# braids_v03_h405_upgrade.net
KiCad netlist of a schematic drawn in EAGLE
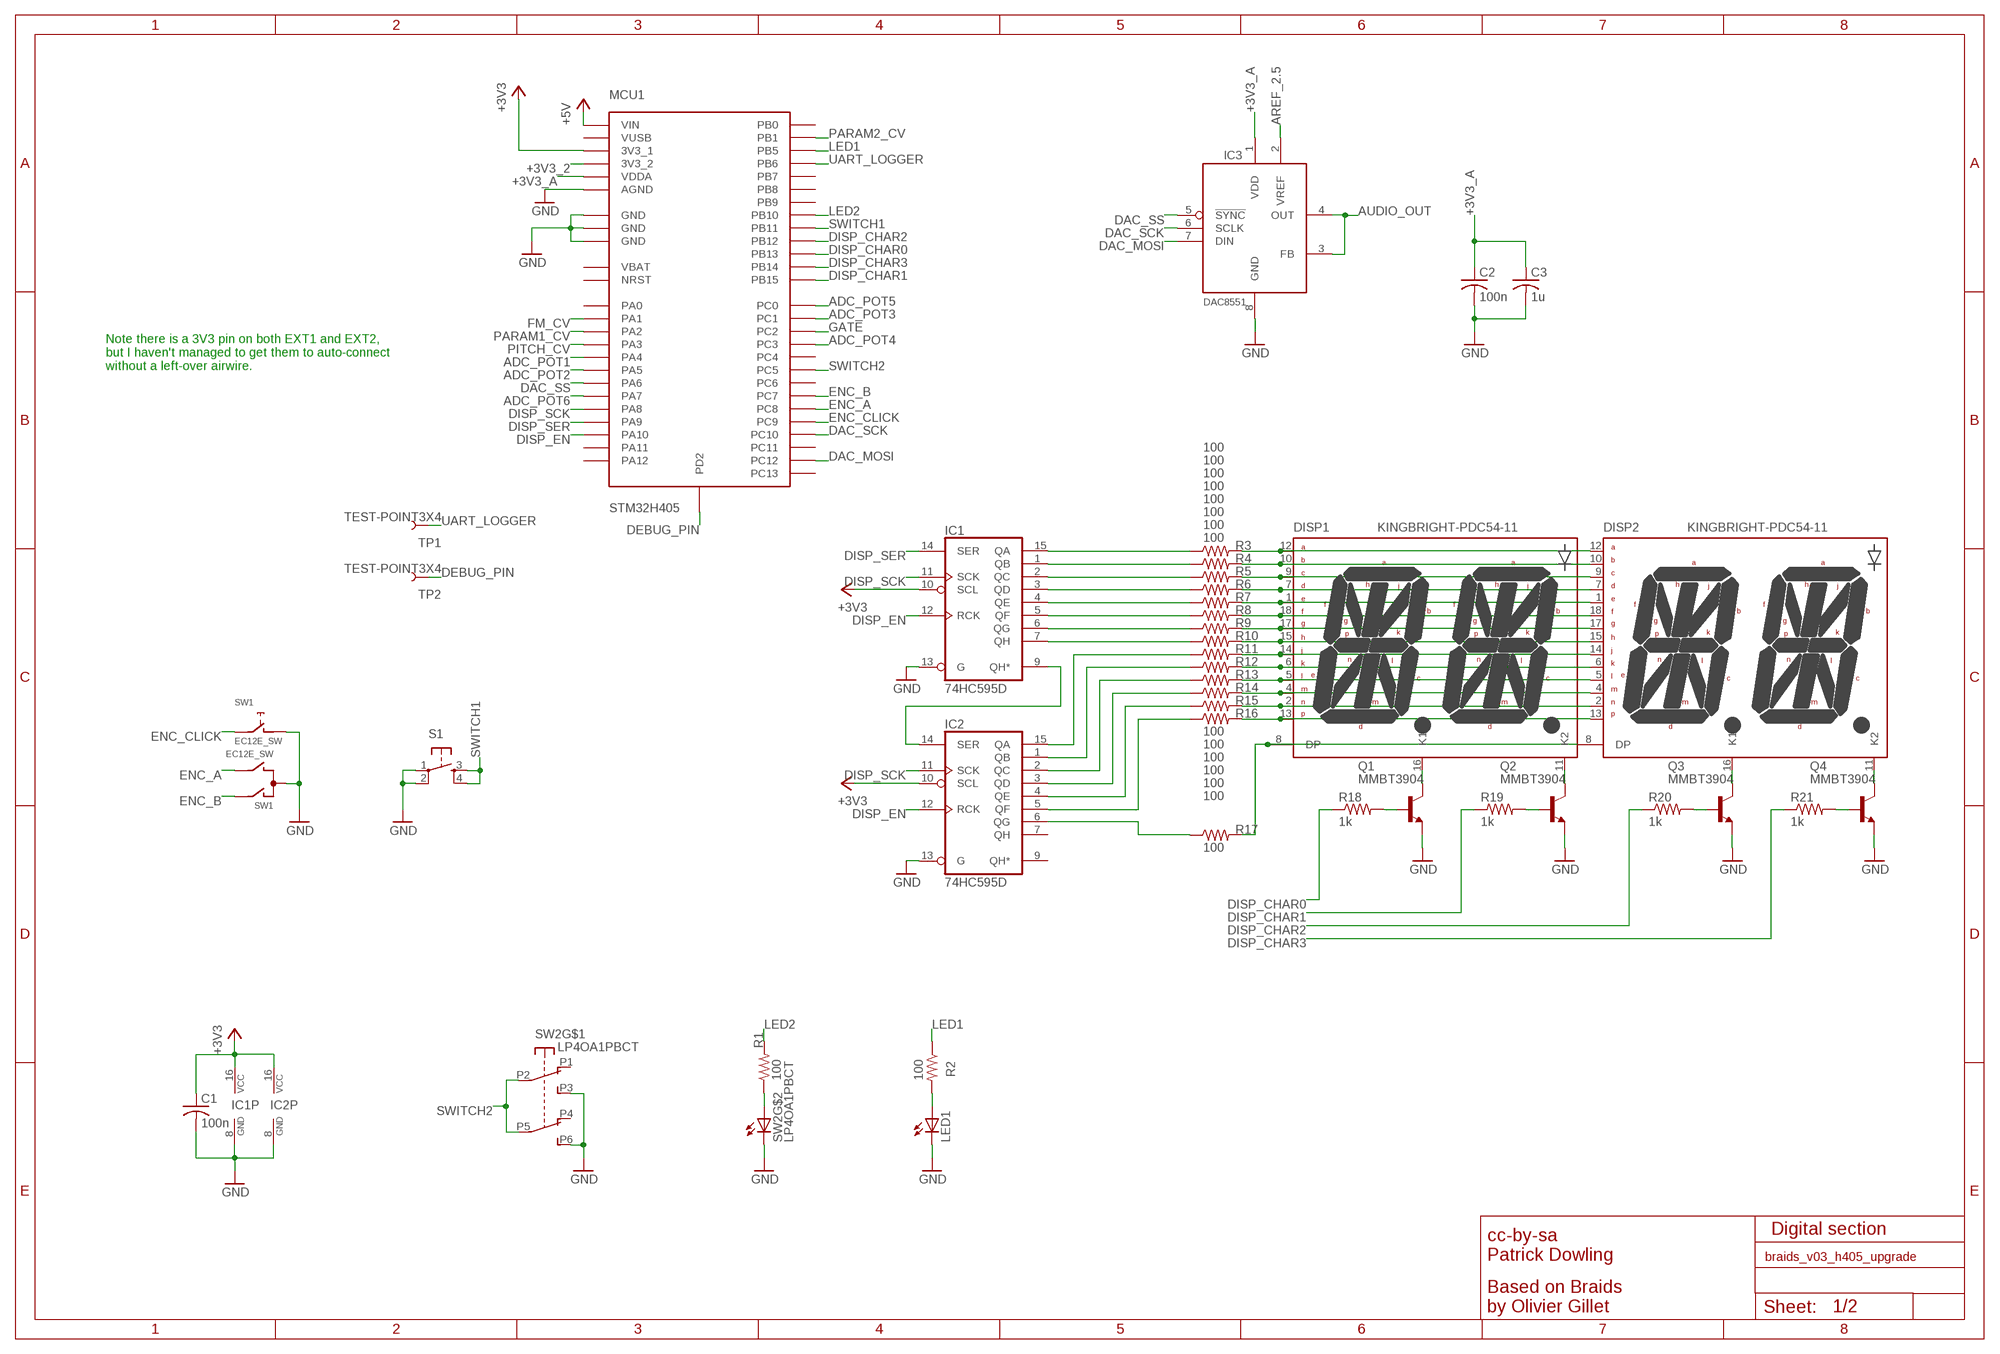
[diagram p0: schematic, sheet 1]
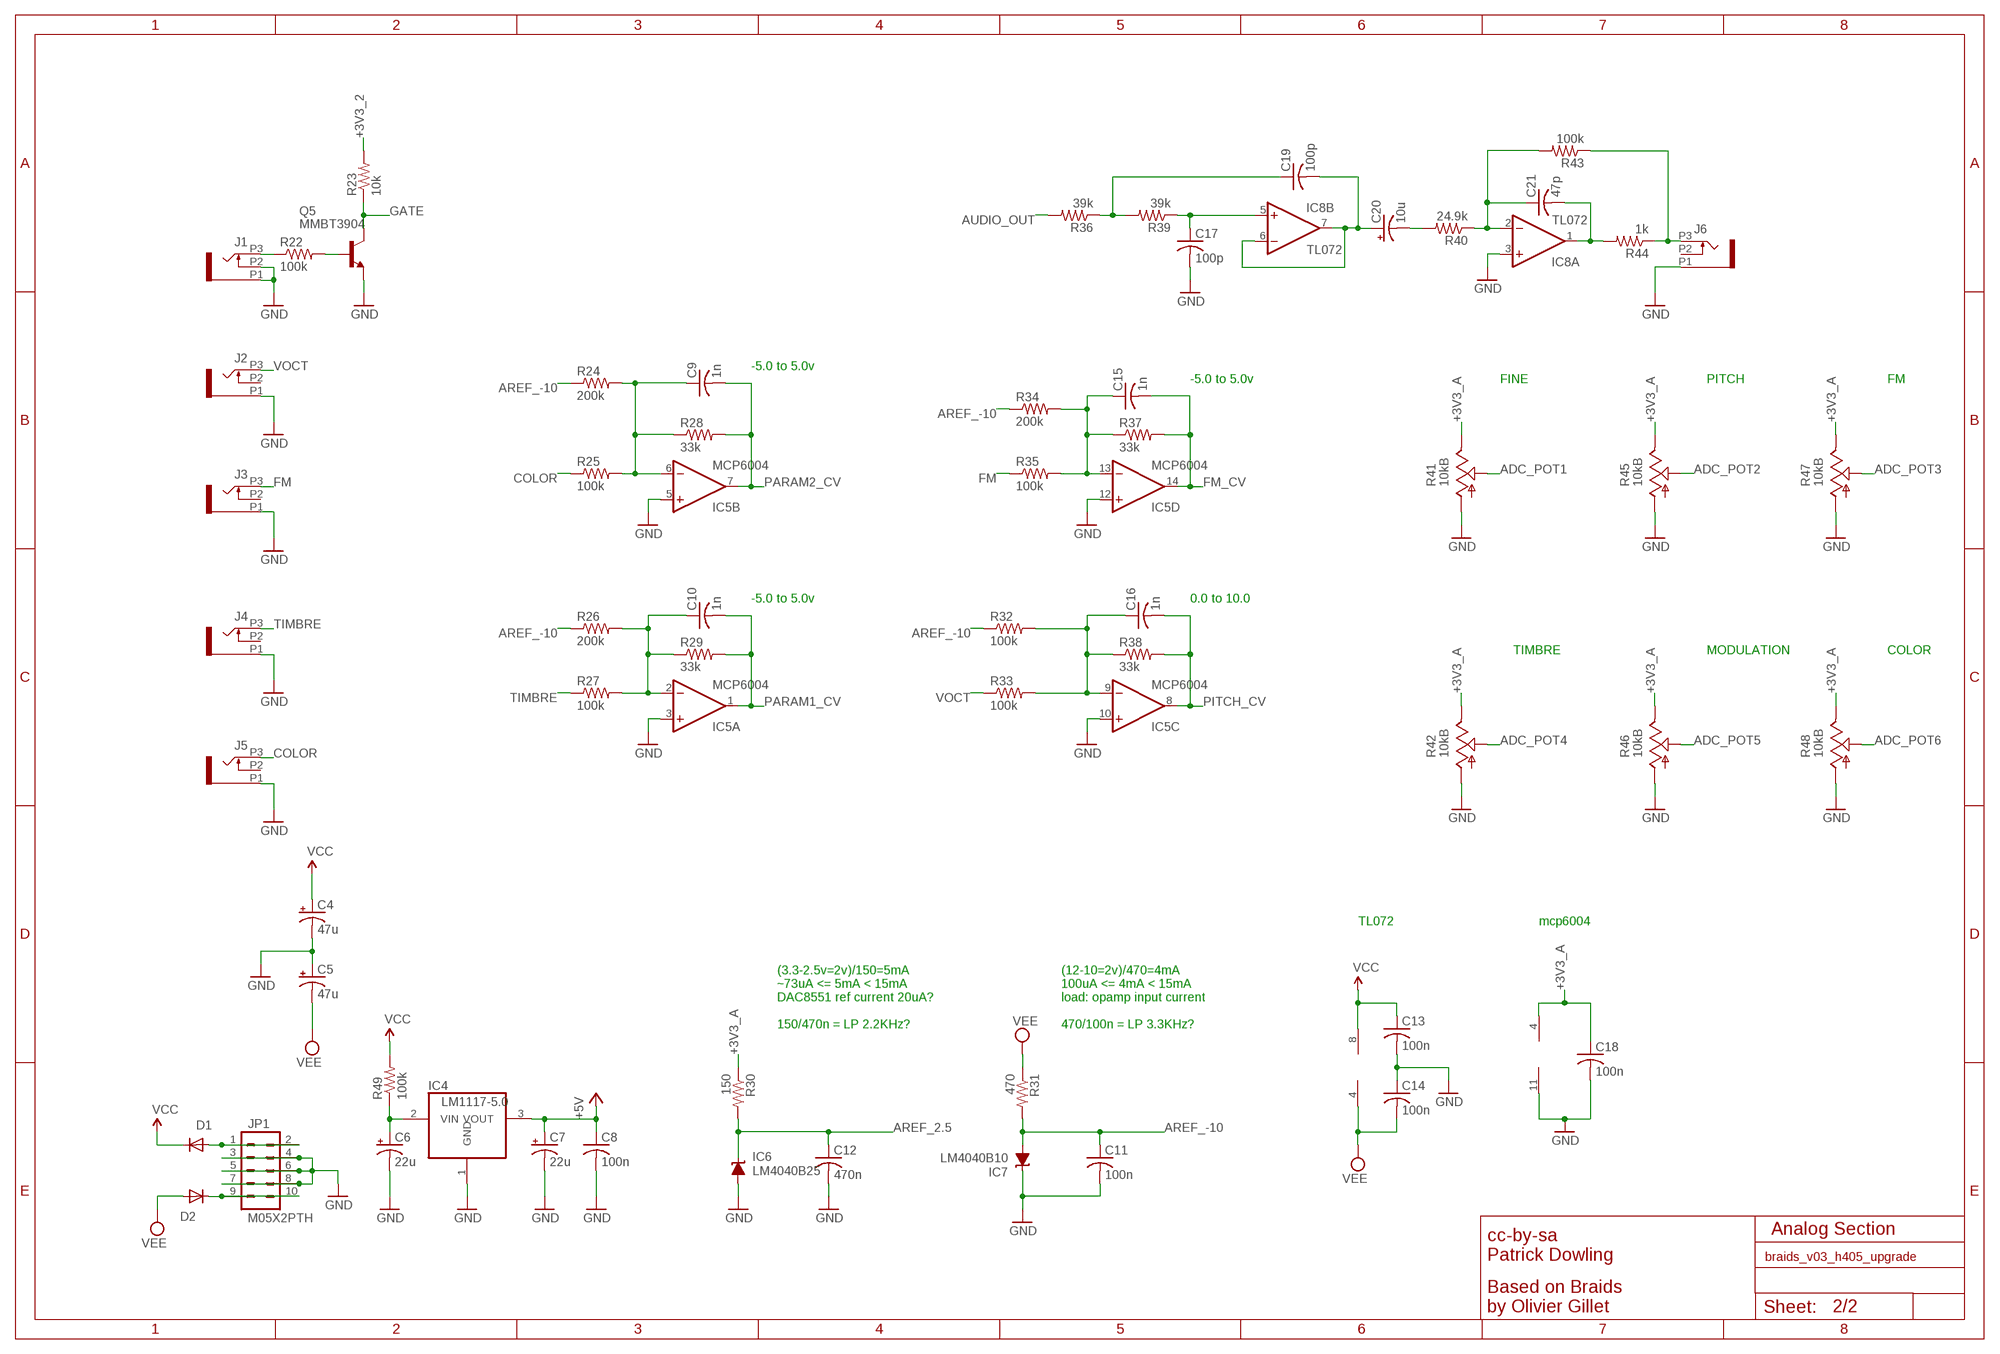
[diagram p1: schematic, sheet 2]

(export (version "E")
  (design (tool "Eeschema 10.0.6"))
  (components
    (comp (ref "C1")
      (value "100n")
      (footprint "eagle-import:C0805")
      (libsource (lib "eagle-import") (part "C-USC0805"))
    )
    (comp (ref "C2")
      (value "100n")
      (footprint "eagle-import:C0805")
      (libsource (lib "eagle-import") (part "C-USC0805"))
    )
    (comp (ref "C3")
      (value "1u")
      (footprint "eagle-import:C0805")
      (libsource (lib "eagle-import") (part "C-USC0805"))
    )
    (comp (ref "DISP1")
      (value "KINGBRIGHT-PDC54-11")
      (footprint "eagle-import:PDC54")
      (libsource (lib "eagle-import") (part "KINGBRIGHT-PDC54-11"))
    )
    (comp (ref "DISP2")
      (value "KINGBRIGHT-PDC54-11")
      (footprint "eagle-import:PDC54")
      (libsource (lib "eagle-import") (part "KINGBRIGHT-PDC54-11"))
    )
    (comp (ref "IC1")
      (value "74HC595D")
      (footprint "eagle-import:SO16")
      (libsource (lib "eagle-import") (part "74595DHC"))
    )
    (comp (ref "IC2")
      (value "74HC595D")
      (footprint "eagle-import:SO16")
      (libsource (lib "eagle-import") (part "74595DHC"))
    )
    (comp (ref "IC3")
      (value "DAC8551")
      (footprint "eagle-import:MSOP-8")
      (libsource (lib "eagle-import") (part "DAC855X"))
    )
    (comp (ref "LED1")
      (value "LED3MM")
      (footprint "eagle-import:LED3MM")
      (libsource (lib "eagle-import") (part "LED3MM"))
    )
    (comp (ref "MCU1")
      (value "STM32H405")
      (footprint "eagle-import:STM32H103")
      (libsource (lib "eagle-import") (part "STM32H103"))
    )
    (comp (ref "Q1")
      (value "MMBT3904")
      (footprint "eagle-import:SOT23-BEC")
      (libsource (lib "eagle-import") (part "-NPN-SOT23-BECMMBT3904LT1"))
    )
    (comp (ref "Q2")
      (value "MMBT3904")
      (footprint "eagle-import:SOT23-BEC")
      (libsource (lib "eagle-import") (part "-NPN-SOT23-BECMMBT3904LT1"))
    )
    (comp (ref "Q3")
      (value "MMBT3904")
      (footprint "eagle-import:SOT23-BEC")
      (libsource (lib "eagle-import") (part "-NPN-SOT23-BECMMBT3904LT1"))
    )
    (comp (ref "Q4")
      (value "MMBT3904")
      (footprint "eagle-import:SOT23-BEC")
      (libsource (lib "eagle-import") (part "-NPN-SOT23-BECMMBT3904LT1"))
    )
    (comp (ref "R1")
      (value "100")
      (footprint "eagle-import:R0805")
      (libsource (lib "eagle-import") (part "R-US_R0805"))
    )
    (comp (ref "R2")
      (value "100")
      (footprint "eagle-import:R0603")
      (libsource (lib "eagle-import") (part "R-US_R0603"))
    )
    (comp (ref "R3")
      (value "100")
      (footprint "eagle-import:R0603")
      (libsource (lib "eagle-import") (part "R-US_R0603"))
    )
    (comp (ref "R4")
      (value "100")
      (footprint "eagle-import:R0603")
      (libsource (lib "eagle-import") (part "R-US_R0603"))
    )
    (comp (ref "R5")
      (value "100")
      (footprint "eagle-import:R0603")
      (libsource (lib "eagle-import") (part "R-US_R0603"))
    )
    (comp (ref "R6")
      (value "100")
      (footprint "eagle-import:R0603")
      (libsource (lib "eagle-import") (part "R-US_R0603"))
    )
    (comp (ref "R7")
      (value "100")
      (footprint "eagle-import:R0603")
      (libsource (lib "eagle-import") (part "R-US_R0603"))
    )
    (comp (ref "R8")
      (value "100")
      (footprint "eagle-import:R0603")
      (libsource (lib "eagle-import") (part "R-US_R0603"))
    )
    (comp (ref "R9")
      (value "100")
      (footprint "eagle-import:R0603")
      (libsource (lib "eagle-import") (part "R-US_R0603"))
    )
    (comp (ref "R10")
      (value "100")
      (footprint "eagle-import:R0603")
      (libsource (lib "eagle-import") (part "R-US_R0603"))
    )
    (comp (ref "R11")
      (value "100")
      (footprint "eagle-import:R0603")
      (libsource (lib "eagle-import") (part "R-US_R0603"))
    )
    (comp (ref "R12")
      (value "100")
      (footprint "eagle-import:R0603")
      (libsource (lib "eagle-import") (part "R-US_R0603"))
    )
    (comp (ref "R13")
      (value "100")
      (footprint "eagle-import:R0603")
      (libsource (lib "eagle-import") (part "R-US_R0603"))
    )
    (comp (ref "R14")
      (value "100")
      (footprint "eagle-import:R0603")
      (libsource (lib "eagle-import") (part "R-US_R0603"))
    )
    (comp (ref "R15")
      (value "100")
      (footprint "eagle-import:R0603")
      (libsource (lib "eagle-import") (part "R-US_R0603"))
    )
    (comp (ref "R16")
      (value "100")
      (footprint "eagle-import:R0603")
      (libsource (lib "eagle-import") (part "R-US_R0603"))
    )
    (comp (ref "R17")
      (value "100")
      (footprint "eagle-import:R0603")
      (libsource (lib "eagle-import") (part "R-US_R0603"))
    )
    (comp (ref "R18")
      (value "1k")
      (footprint "eagle-import:R0603")
      (libsource (lib "eagle-import") (part "R-US_R0603"))
    )
    (comp (ref "R19")
      (value "1k")
      (footprint "eagle-import:R0603")
      (libsource (lib "eagle-import") (part "R-US_R0603"))
    )
    (comp (ref "R20")
      (value "1k")
      (footprint "eagle-import:R0603")
      (libsource (lib "eagle-import") (part "R-US_R0603"))
    )
    (comp (ref "R21")
      (value "1k")
      (footprint "eagle-import:R0603")
      (libsource (lib "eagle-import") (part "R-US_R0603"))
    )
    (comp (ref "S1")
      (value "TAC_SWITCHPTH")
      (footprint "eagle-import:TACTILE-PTH")
      (libsource (lib "eagle-import") (part "TAC_SWITCHPTH"))
    )
    (comp (ref "SW1")
      (value "EC12E_SW")
      (footprint "eagle-import:ALPS_EC12E_SW")
      (libsource (lib "eagle-import") (part "EC12E_SW"))
    )
    (comp (ref "SW2")
      (value "LP4OA1PBCT")
      (footprint "eagle-import:LP4OA1PBCT")
      (libsource (lib "eagle-import") (part "LP4OA1PBCT"))
    )
    (comp (ref "TP1")
      (value "TEST-POINT3X4")
      (footprint "eagle-import:PAD.03X.04")
      (libsource (lib "eagle-import") (part "TEST-POINT3X4"))
    )
    (comp (ref "TP2")
      (value "TEST-POINT3X4")
      (footprint "eagle-import:PAD.03X.04")
      (libsource (lib "eagle-import") (part "TEST-POINT3X4"))
    )
    (comp (ref "C4")
      (value "47u")
      (footprint "eagle-import:PANASONIC_D")
      (libsource (lib "eagle-import") (part "CPOL-USD"))
    )
    (comp (ref "C5")
      (value "47u")
      (footprint "eagle-import:PANASONIC_D")
      (libsource (lib "eagle-import") (part "CPOL-USD"))
    )
    (comp (ref "C6")
      (value "22u")
      (footprint "eagle-import:PANASONIC_C")
      (libsource (lib "eagle-import") (part "CPOL-USC"))
    )
    (comp (ref "C7")
      (value "22u")
      (footprint "eagle-import:PANASONIC_C")
      (libsource (lib "eagle-import") (part "CPOL-USC"))
    )
    (comp (ref "C8")
      (value "100n")
      (footprint "eagle-import:C0805")
      (libsource (lib "eagle-import") (part "C-USC0805"))
    )
    (comp (ref "C9")
      (value "1n")
      (footprint "eagle-import:C0805")
      (libsource (lib "eagle-import") (part "C-USC0805"))
    )
    (comp (ref "C10")
      (value "1n")
      (footprint "eagle-import:C0805")
      (libsource (lib "eagle-import") (part "C-USC0805"))
    )
    (comp (ref "C11")
      (value "100n")
      (footprint "eagle-import:C0805")
      (libsource (lib "eagle-import") (part "C-USC0805"))
    )
    (comp (ref "C12")
      (value "470n")
      (footprint "eagle-import:C0805")
      (libsource (lib "eagle-import") (part "C-USC0805"))
    )
    (comp (ref "C13")
      (value "100n")
      (footprint "eagle-import:C0805")
      (libsource (lib "eagle-import") (part "C-USC0805"))
    )
    (comp (ref "C14")
      (value "100n")
      (footprint "eagle-import:C0805")
      (libsource (lib "eagle-import") (part "C-USC0805"))
    )
    (comp (ref "C15")
      (value "1n")
      (footprint "eagle-import:C0805")
      (libsource (lib "eagle-import") (part "C-USC0805"))
    )
    (comp (ref "C16")
      (value "1n")
      (footprint "eagle-import:C0805")
      (libsource (lib "eagle-import") (part "C-USC0805"))
    )
    (comp (ref "C17")
      (value "100p")
      (footprint "eagle-import:C0805")
      (libsource (lib "eagle-import") (part "C-USC0805"))
    )
    (comp (ref "C18")
      (value "100n")
      (footprint "eagle-import:C0805")
      (libsource (lib "eagle-import") (part "C-USC0805"))
    )
    (comp (ref "C19")
      (value "100p")
      (footprint "eagle-import:C0805")
      (libsource (lib "eagle-import") (part "C-USC0805"))
    )
    (comp (ref "C20")
      (value "10u")
      (footprint "eagle-import:E2-5")
      (libsource (lib "eagle-import") (part "CPOL-USE2-5"))
    )
    (comp (ref "C21")
      (value "47p")
      (footprint "eagle-import:C0805")
      (libsource (lib "eagle-import") (part "C-USC0805"))
    )
    (comp (ref "D1")
      (value "1N5819HW")
      (footprint "eagle-import:SOD123")
      (libsource (lib "eagle-import") (part "DIODE-SOD123"))
    )
    (comp (ref "D2")
      (value "1N5819HW")
      (footprint "eagle-import:SOD123")
      (libsource (lib "eagle-import") (part "DIODE-SOD123"))
    )
    (comp (ref "IC4")
      (value "LM1117-5.0")
      (footprint "eagle-import:TO252")
      (libsource (lib "eagle-import") (part "REG1117T"))
    )
    (comp (ref "IC5")
      (value "MCP6004")
      (footprint "eagle-import:SO14")
      (libsource (lib "eagle-import") (part "TL074D"))
    )
    (comp (ref "IC6")
      (value "LM4040B25")
      (footprint "eagle-import:DBZ_R-PDSO-G3")
      (libsource (lib "eagle-import") (part "LM4041DBZB12"))
    )
    (comp (ref "IC7")
      (value "LM4040B10")
      (footprint "eagle-import:DBZ_R-PDSO-G3")
      (libsource (lib "eagle-import") (part "LM4041DBZB12"))
    )
    (comp (ref "IC8")
      (value "TL072")
      (footprint "eagle-import:SO08")
      (libsource (lib "eagle-import") (part "TL072D"))
    )
    (comp (ref "J1")
      (value "PJ301_THONKICONN6")
      (footprint "eagle-import:WQP_PJ_301M6")
      (libsource (lib "eagle-import") (part "PJ301_THONKICONN6"))
    )
    (comp (ref "J2")
      (value "PJ301_THONKICONN6")
      (footprint "eagle-import:WQP_PJ_301M6")
      (libsource (lib "eagle-import") (part "PJ301_THONKICONN6"))
    )
    (comp (ref "J3")
      (value "PJ301_THONKICONN6")
      (footprint "eagle-import:WQP_PJ_301M6")
      (libsource (lib "eagle-import") (part "PJ301_THONKICONN6"))
    )
    (comp (ref "J4")
      (value "PJ301_THONKICONN6")
      (footprint "eagle-import:WQP_PJ_301M6")
      (libsource (lib "eagle-import") (part "PJ301_THONKICONN6"))
    )
    (comp (ref "J5")
      (value "PJ301_THONKICONN6")
      (footprint "eagle-import:WQP_PJ_301M6")
      (libsource (lib "eagle-import") (part "PJ301_THONKICONN6"))
    )
    (comp (ref "J6")
      (value "PJ301_THONKICONN6")
      (footprint "eagle-import:WQP_PJ_301M6")
      (libsource (lib "eagle-import") (part "PJ301_THONKICONN6"))
    )
    (comp (ref "JP1")
      (value "M05X2PTH")
      (footprint "eagle-import:AVR_ICSP")
      (libsource (lib "eagle-import") (part "M05X2PTH"))
    )
    (comp (ref "Q5")
      (value "MMBT3904")
      (footprint "eagle-import:SOT23-BEC")
      (libsource (lib "eagle-import") (part "-NPN-SOT23-BECMMBT3904LT1"))
    )
    (comp (ref "R22")
      (value "100k")
      (footprint "eagle-import:R0805")
      (libsource (lib "eagle-import") (part "R-US_R0805"))
    )
    (comp (ref "R23")
      (value "10k")
      (footprint "eagle-import:R0805")
      (libsource (lib "eagle-import") (part "R-US_R0805"))
    )
    (comp (ref "R24")
      (value "200k")
      (footprint "eagle-import:R0805")
      (libsource (lib "eagle-import") (part "R-US_R0805"))
    )
    (comp (ref "R25")
      (value "100k")
      (footprint "eagle-import:R0805")
      (libsource (lib "eagle-import") (part "R-US_R0805"))
    )
    (comp (ref "R26")
      (value "200k")
      (footprint "eagle-import:R0805")
      (libsource (lib "eagle-import") (part "R-US_R0805"))
    )
    (comp (ref "R27")
      (value "100k")
      (footprint "eagle-import:R0805")
      (libsource (lib "eagle-import") (part "R-US_R0805"))
    )
    (comp (ref "R28")
      (value "33k")
      (footprint "eagle-import:R0805")
      (libsource (lib "eagle-import") (part "R-US_R0805"))
    )
    (comp (ref "R29")
      (value "33k")
      (footprint "eagle-import:R0805")
      (libsource (lib "eagle-import") (part "R-US_R0805"))
    )
    (comp (ref "R30")
      (value "150")
      (footprint "eagle-import:R0805")
      (libsource (lib "eagle-import") (part "R-US_R0805"))
    )
    (comp (ref "R31")
      (value "470")
      (footprint "eagle-import:R0805")
      (libsource (lib "eagle-import") (part "R-US_R0805"))
    )
    (comp (ref "R32")
      (value "100k")
      (footprint "eagle-import:R0805")
      (libsource (lib "eagle-import") (part "R-US_R0805"))
    )
    (comp (ref "R33")
      (value "100k")
      (footprint "eagle-import:R0805")
      (libsource (lib "eagle-import") (part "R-US_R0805"))
    )
    (comp (ref "R34")
      (value "200k")
      (footprint "eagle-import:R0805")
      (libsource (lib "eagle-import") (part "R-US_R0805"))
    )
    (comp (ref "R35")
      (value "100k")
      (footprint "eagle-import:R0805")
      (libsource (lib "eagle-import") (part "R-US_R0805"))
    )
    (comp (ref "R36")
      (value "39k")
      (footprint "eagle-import:R0805")
      (libsource (lib "eagle-import") (part "R-US_R0805"))
    )
    (comp (ref "R37")
      (value "33k")
      (footprint "eagle-import:R0805")
      (libsource (lib "eagle-import") (part "R-US_R0805"))
    )
    (comp (ref "R38")
      (value "33k")
      (footprint "eagle-import:R0805")
      (libsource (lib "eagle-import") (part "R-US_R0805"))
    )
    (comp (ref "R39")
      (value "39k")
      (footprint "eagle-import:R0805")
      (libsource (lib "eagle-import") (part "R-US_R0805"))
    )
    (comp (ref "R40")
      (value "24.9k")
      (footprint "eagle-import:R0805")
      (libsource (lib "eagle-import") (part "R-US_R0805"))
    )
    (comp (ref "R41")
      (value "10kB")
      (footprint "eagle-import:ALPS_POT_VERTICAL_PS")
      (libsource (lib "eagle-import") (part "POT_USVERTICAL_PS"))
    )
    (comp (ref "R42")
      (value "10kB")
      (footprint "eagle-import:ALPS_POT_VERTICAL_PS")
      (libsource (lib "eagle-import") (part "POT_USVERTICAL_PS"))
    )
    (comp (ref "R43")
      (value "100k")
      (footprint "eagle-import:R0805")
      (libsource (lib "eagle-import") (part "R-US_R0805"))
    )
    (comp (ref "R44")
      (value "1k")
      (footprint "eagle-import:R0805")
      (libsource (lib "eagle-import") (part "R-US_R0805"))
    )
    (comp (ref "R45")
      (value "10kB")
      (footprint "eagle-import:ALPS_POT_VERTICAL_PS")
      (libsource (lib "eagle-import") (part "POT_USVERTICAL_PS"))
    )
    (comp (ref "R46")
      (value "10kB")
      (footprint "eagle-import:ALPS_POT_VERTICAL_PS")
      (libsource (lib "eagle-import") (part "POT_USVERTICAL_PS"))
    )
    (comp (ref "R47")
      (value "10kB")
      (footprint "eagle-import:ALPS_POT_VERTICAL_PS")
      (libsource (lib "eagle-import") (part "POT_USVERTICAL_PS"))
    )
    (comp (ref "R48")
      (value "10kB")
      (footprint "eagle-import:ALPS_POT_VERTICAL_PS")
      (libsource (lib "eagle-import") (part "POT_USVERTICAL_PS"))
    )
    (comp (ref "R49")
      (value "100k")
      (footprint "eagle-import:R1206")
      (libsource (lib "eagle-import") (part "R-US_R1206"))
    )
  )
  (nets
    (net (code "1") (name "+3V3") (class "Default")
      (node (ref "C1") (pin "1") (pinfunction "1_1") (pintype "passive"))
      (node (ref "IC1") (pin "10") (pinfunction "SCL_10") (pintype "input"))
      (node (ref "IC1") (pin "16") (pinfunction "VCC_16") (pintype "power_in"))
      (node (ref "IC2") (pin "10") (pinfunction "SCL_10") (pintype "input"))
      (node (ref "IC2") (pin "16") (pinfunction "VCC_16") (pintype "power_in"))
      (node (ref "MCU1") (pin "EXT1-5") (pinfunction "3V3_1_EXT1-5") (pintype "power_in"))
    )
    (net (code "2") (name "+3V3_2") (class "Default")
      (node (ref "MCU1") (pin "EXT2-5") (pinfunction "3V3_2_EXT2-5") (pintype "power_in"))
      (node (ref "R23") (pin "2") (pinfunction "2_2") (pintype "passive"))
    )
    (net (code "3") (name "+3V3_A") (class "Default")
      (node (ref "C18") (pin "1") (pinfunction "1_1") (pintype "passive"))
      (node (ref "C2") (pin "1") (pinfunction "1_1") (pintype "passive"))
      (node (ref "C3") (pin "1") (pinfunction "1_1") (pintype "passive"))
      (node (ref "IC3") (pin "1") (pinfunction "VDD_1") (pintype "power_in"))
      (node (ref "IC5") (pin "4") (pinfunction "V+_4") (pintype "power_in"))
      (node (ref "MCU1") (pin "EXT2-1") (pinfunction "VDDA_EXT2-1") (pintype "power_in"))
      (node (ref "R30") (pin "1") (pinfunction "1_1") (pintype "passive"))
      (node (ref "R41") (pin "P$1") (pinfunction "E_P$1") (pintype "passive"))
      (node (ref "R42") (pin "P$1") (pinfunction "E_P$1") (pintype "passive"))
      (node (ref "R45") (pin "P$1") (pinfunction "E_P$1") (pintype "passive"))
      (node (ref "R46") (pin "P$1") (pinfunction "E_P$1") (pintype "passive"))
      (node (ref "R47") (pin "P$1") (pinfunction "E_P$1") (pintype "passive"))
      (node (ref "R48") (pin "P$1") (pinfunction "E_P$1") (pintype "passive"))
    )
    (net (code "4") (name "+5V") (class "Default")
      (node (ref "C7") (pin "+") (pinfunction "+_+") (pintype "passive"))
      (node (ref "C8") (pin "1") (pinfunction "1_1") (pintype "passive"))
      (node (ref "IC4") (pin "3") (pinfunction "VOUT_3") (pintype "output"))
      (node (ref "MCU1") (pin "EXT2-26") (pinfunction "VIN_EXT2-26") (pintype "power_in"))
    )
    (net (code "5") (name "ADC_POT1") (class "Default")
      (node (ref "MCU1") (pin "EXT2-11") (pinfunction "PA4_EXT2-11") (pintype "bidirectional"))
      (node (ref "R41") (pin "P$2") (pinfunction "S_P$2") (pintype "passive"))
    )
    (net (code "6") (name "ADC_POT2") (class "Default")
      (node (ref "MCU1") (pin "EXT1-18") (pinfunction "PA5_EXT1-18") (pintype "bidirectional"))
      (node (ref "R45") (pin "P$2") (pinfunction "S_P$2") (pintype "passive"))
    )
    (net (code "7") (name "ADC_POT3") (class "Default")
      (node (ref "MCU1") (pin "EXT1-20") (pinfunction "PC1_EXT1-20") (pintype "bidirectional"))
      (node (ref "R47") (pin "P$2") (pinfunction "S_P$2") (pintype "passive"))
    )
    (net (code "8") (name "ADC_POT4") (class "Default")
      (node (ref "MCU1") (pin "EXT2-9") (pinfunction "PC3_EXT2-9") (pintype "bidirectional"))
      (node (ref "R42") (pin "P$2") (pinfunction "S_P$2") (pintype "passive"))
    )
    (net (code "9") (name "ADC_POT5") (class "Default")
      (node (ref "MCU1") (pin "EXT1-19") (pinfunction "PC0_EXT1-19") (pintype "bidirectional"))
      (node (ref "R46") (pin "P$2") (pinfunction "S_P$2") (pintype "passive"))
    )
    (net (code "10") (name "ADC_POT6") (class "Default")
      (node (ref "MCU1") (pin "EXT1-22") (pinfunction "PA7_EXT1-22") (pintype "bidirectional"))
      (node (ref "R48") (pin "P$2") (pinfunction "S_P$2") (pintype "passive"))
    )
    (net (code "11") (name "AREF_-10") (class "Default")
      (node (ref "C11") (pin "1") (pinfunction "1_1") (pintype "passive"))
      (node (ref "IC7") (pin "2") (pinfunction "A_2") (pintype "passive"))
      (node (ref "R24") (pin "1") (pinfunction "1_1") (pintype "passive"))
      (node (ref "R26") (pin "1") (pinfunction "1_1") (pintype "passive"))
      (node (ref "R31") (pin "2") (pinfunction "2_2") (pintype "passive"))
      (node (ref "R32") (pin "1") (pinfunction "1_1") (pintype "passive"))
      (node (ref "R34") (pin "1") (pinfunction "1_1") (pintype "passive"))
    )
    (net (code "12") (name "AREF_2.5") (class "Default")
      (node (ref "C12") (pin "1") (pinfunction "1_1") (pintype "passive"))
      (node (ref "IC3") (pin "2") (pinfunction "VREF_2") (pintype "power_in"))
      (node (ref "IC6") (pin "1") (pinfunction "C_1") (pintype "passive"))
      (node (ref "R30") (pin "2") (pinfunction "2_2") (pintype "passive"))
    )
    (net (code "13") (name "AUDIO_OUT") (class "Default")
      (node (ref "IC3") (pin "3") (pinfunction "FB_3") (pintype "input"))
      (node (ref "IC3") (pin "4") (pinfunction "OUT_4") (pintype "output"))
      (node (ref "R36") (pin "2") (pinfunction "2_2") (pintype "passive"))
    )
    (net (code "14") (name "COLOR") (class "Default")
      (node (ref "J5") (pin "P3") (pinfunction "3_P3") (pintype "passive"))
      (node (ref "R25") (pin "1") (pinfunction "1_1") (pintype "passive"))
    )
    (net (code "15") (name "DAC_MOSI") (class "Default")
      (node (ref "IC3") (pin "7") (pinfunction "DIN_7") (pintype "bidirectional"))
      (node (ref "MCU1") (pin "EXT1-10") (pinfunction "PC12_EXT1-10") (pintype "bidirectional"))
    )
    (net (code "16") (name "DAC_SCK") (class "Default")
      (node (ref "IC3") (pin "6") (pinfunction "SCLK_6") (pintype "bidirectional"))
      (node (ref "MCU1") (pin "EXT1-8") (pinfunction "PC10_EXT1-8") (pintype "bidirectional"))
    )
    (net (code "17") (name "DAC_SS") (class "Default")
      (node (ref "IC3") (pin "5") (pinfunction "~{SYNC}_5") (pintype "bidirectional"))
      (node (ref "MCU1") (pin "EXT1-14") (pinfunction "PA6_EXT1-14") (pintype "bidirectional"))
    )
    (net (code "18") (name "DEBUG_PIN") (class "Default")
      (node (ref "MCU1") (pin "EXT1-11") (pinfunction "PD2_EXT1-11") (pintype "bidirectional"))
      (node (ref "TP2") (pin "P$1") (pinfunction "1_P$1") (pintype "bidirectional"))
    )
    (net (code "19") (name "DISP_CHAR0") (class "Default")
      (node (ref "MCU1") (pin "EXT2-16") (pinfunction "PB13_EXT2-16") (pintype "bidirectional"))
      (node (ref "R18") (pin "1") (pinfunction "1_1") (pintype "passive"))
    )
    (net (code "20") (name "DISP_CHAR1") (class "Default")
      (node (ref "MCU1") (pin "EXT2-19") (pinfunction "PB15_EXT2-19") (pintype "bidirectional"))
      (node (ref "R19") (pin "1") (pinfunction "1_1") (pintype "passive"))
    )
    (net (code "21") (name "DISP_CHAR2") (class "Default")
      (node (ref "MCU1") (pin "EXT2-17") (pinfunction "PB12_EXT2-17") (pintype "bidirectional"))
      (node (ref "R20") (pin "1") (pinfunction "1_1") (pintype "passive"))
    )
    (net (code "22") (name "DISP_CHAR3") (class "Default")
      (node (ref "MCU1") (pin "EXT2-18") (pinfunction "PB14_EXT2-18") (pintype "bidirectional"))
      (node (ref "R21") (pin "1") (pinfunction "1_1") (pintype "passive"))
    )
    (net (code "23") (name "DISP_EN") (class "Default")
      (node (ref "IC1") (pin "12") (pinfunction "RCK_12") (pintype "input"))
      (node (ref "IC2") (pin "12") (pinfunction "RCK_12") (pintype "input"))
      (node (ref "MCU1") (pin "EXT1-7") (pinfunction "PA10_EXT1-7") (pintype "bidirectional"))
    )
    (net (code "24") (name "DISP_SCK") (class "Default")
      (node (ref "IC1") (pin "11") (pinfunction "SCK_11") (pintype "input"))
      (node (ref "IC2") (pin "11") (pinfunction "SCK_11") (pintype "input"))
      (node (ref "MCU1") (pin "EXT1-2") (pinfunction "PA8_EXT1-2") (pintype "bidirectional"))
    )
    (net (code "25") (name "DISP_SER") (class "Default")
      (node (ref "IC1") (pin "14") (pinfunction "SER_14") (pintype "input"))
      (node (ref "MCU1") (pin "EXT1-4") (pinfunction "PA9_EXT1-4") (pintype "bidirectional"))
    )
    (net (code "26") (name "ENC_A") (class "Default")
      (node (ref "MCU1") (pin "EXT2-22") (pinfunction "PC8_EXT2-22") (pintype "bidirectional"))
      (node (ref "SW1") (pin "B") (pinfunction "B_B") (pintype "passive"))
    )
    (net (code "27") (name "ENC_B") (class "Default")
      (node (ref "MCU1") (pin "EXT2-21") (pinfunction "PC7_EXT2-21") (pintype "bidirectional"))
      (node (ref "SW1") (pin "A") (pinfunction "A_A") (pintype "passive"))
    )
    (net (code "28") (name "ENC_CLICK") (class "Default")
      (node (ref "MCU1") (pin "EXT2-24") (pinfunction "PC9_EXT2-24") (pintype "bidirectional"))
      (node (ref "SW1") (pin "E") (pinfunction "2_E") (pintype "passive"))
    )
    (net (code "29") (name "FM") (class "Default")
      (node (ref "J3") (pin "P3") (pinfunction "3_P3") (pintype "passive"))
      (node (ref "R35") (pin "1") (pinfunction "1_1") (pintype "passive"))
    )
    (net (code "30") (name "FM_CV") (class "Default")
      (node (ref "C15") (pin "2") (pinfunction "2_2") (pintype "passive"))
      (node (ref "IC5") (pin "14") (pinfunction "OUT_14") (pintype "output"))
      (node (ref "MCU1") (pin "EXT2-8") (pinfunction "PA1_EXT2-8") (pintype "bidirectional"))
      (node (ref "R37") (pin "2") (pinfunction "2_2") (pintype "passive"))
    )
    (net (code "31") (name "GATE") (class "Default")
      (node (ref "MCU1") (pin "EXT2-2") (pinfunction "PC2_EXT2-2") (pintype "bidirectional"))
      (node (ref "Q5") (pin "C") (pinfunction "C_C") (pintype "passive"))
      (node (ref "R23") (pin "1") (pinfunction "1_1") (pintype "passive"))
    )
    (net (code "32") (name "GND") (class "Default")
      (node (ref "C1") (pin "2") (pinfunction "2_2") (pintype "passive"))
      (node (ref "C11") (pin "2") (pinfunction "2_2") (pintype "passive"))
      (node (ref "C12") (pin "2") (pinfunction "2_2") (pintype "passive"))
      (node (ref "C13") (pin "2") (pinfunction "2_2") (pintype "passive"))
      (node (ref "C14") (pin "1") (pinfunction "1_1") (pintype "passive"))
      (node (ref "C17") (pin "2") (pinfunction "2_2") (pintype "passive"))
      (node (ref "C18") (pin "2") (pinfunction "2_2") (pintype "passive"))
      (node (ref "C2") (pin "2") (pinfunction "2_2") (pintype "passive"))
      (node (ref "C3") (pin "2") (pinfunction "2_2") (pintype "passive"))
      (node (ref "C4") (pin "-") (pinfunction "-_-") (pintype "passive"))
      (node (ref "C5") (pin "+") (pinfunction "+_+") (pintype "passive"))
      (node (ref "C6") (pin "-") (pinfunction "-_-") (pintype "passive"))
      (node (ref "C7") (pin "-") (pinfunction "-_-") (pintype "passive"))
      (node (ref "C8") (pin "2") (pinfunction "2_2") (pintype "passive"))
      (node (ref "IC1") (pin "13") (pinfunction "G_13") (pintype "input"))
      (node (ref "IC1") (pin "8") (pinfunction "GND_8") (pintype "power_in"))
      (node (ref "IC2") (pin "13") (pinfunction "G_13") (pintype "input"))
      (node (ref "IC2") (pin "8") (pinfunction "GND_8") (pintype "power_in"))
      (node (ref "IC3") (pin "8") (pinfunction "GND_8") (pintype "power_in"))
      (node (ref "IC4") (pin "1") (pinfunction "GND_1") (pintype "power_in"))
      (node (ref "IC5") (pin "10") (pinfunction "+IN_10") (pintype "input"))
      (node (ref "IC5") (pin "11") (pinfunction "V-_11") (pintype "power_in"))
      (node (ref "IC5") (pin "12") (pinfunction "+IN_12") (pintype "input"))
      (node (ref "IC5") (pin "3") (pinfunction "+IN_3") (pintype "input"))
      (node (ref "IC5") (pin "5") (pinfunction "+IN_5") (pintype "input"))
      (node (ref "IC6") (pin "2") (pinfunction "A_2") (pintype "passive"))
      (node (ref "IC7") (pin "1") (pinfunction "C_1") (pintype "passive"))
      (node (ref "IC8") (pin "3") (pinfunction "+IN_3") (pintype "input"))
      (node (ref "J1") (pin "P1") (pinfunction "1_P1") (pintype "passive"))
      (node (ref "J1") (pin "P2") (pinfunction "2_P2") (pintype "passive"))
      (node (ref "J2") (pin "P1") (pinfunction "1_P1") (pintype "passive"))
      (node (ref "J3") (pin "P1") (pinfunction "1_P1") (pintype "passive"))
      (node (ref "J4") (pin "P1") (pinfunction "1_P1") (pintype "passive"))
      (node (ref "J5") (pin "P1") (pinfunction "1_P1") (pintype "passive"))
      (node (ref "J6") (pin "P1") (pinfunction "1_P1") (pintype "passive"))
      (node (ref "JP1") (pin "3") (pinfunction "3_3") (pintype "passive"))
      (node (ref "JP1") (pin "4") (pinfunction "4_4") (pintype "passive"))
      (node (ref "JP1") (pin "5") (pinfunction "5_5") (pintype "passive"))
      (node (ref "JP1") (pin "6") (pinfunction "6_6") (pintype "passive"))
      (node (ref "JP1") (pin "7") (pinfunction "7_7") (pintype "passive"))
      (node (ref "JP1") (pin "8") (pinfunction "8_8") (pintype "passive"))
      (node (ref "LED1") (pin "K") (pinfunction "C_K") (pintype "passive"))
      (node (ref "MCU1") (pin "EXT1-6") (pinfunction "GND_EXT1-6") (pintype "power_in"))
      (node (ref "MCU1") (pin "EXT2-25") (pinfunction "GND_EXT2-25") (pintype "power_in"))
      (node (ref "MCU1") (pin "EXT2-3") (pinfunction "AGND_EXT2-3") (pintype "power_in"))
      (node (ref "MCU1") (pin "EXT2-6") (pinfunction "GND_EXT2-6") (pintype "power_in"))
      (node (ref "Q1") (pin "E") (pinfunction "E_E") (pintype "passive"))
      (node (ref "Q2") (pin "E") (pinfunction "E_E") (pintype "passive"))
      (node (ref "Q3") (pin "E") (pinfunction "E_E") (pintype "passive"))
      (node (ref "Q4") (pin "E") (pinfunction "E_E") (pintype "passive"))
      (node (ref "Q5") (pin "E") (pinfunction "E_E") (pintype "passive"))
      (node (ref "R41") (pin "P$3") (pinfunction "A_P$3") (pintype "passive"))
      (node (ref "R42") (pin "P$3") (pinfunction "A_P$3") (pintype "passive"))
      (node (ref "R45") (pin "P$3") (pinfunction "A_P$3") (pintype "passive"))
      (node (ref "R46") (pin "P$3") (pinfunction "A_P$3") (pintype "passive"))
      (node (ref "R47") (pin "P$3") (pinfunction "A_P$3") (pintype "passive"))
      (node (ref "R48") (pin "P$3") (pinfunction "A_P$3") (pintype "passive"))
      (node (ref "S1") (pin "1") (pinfunction "1_1") (pintype "passive"))
      (node (ref "S1") (pin "2") (pinfunction "2_2") (pintype "passive"))
      (node (ref "SW1") (pin "C") (pinfunction "C_C") (pintype "passive"))
      (node (ref "SW1") (pin "D") (pinfunction "1_D") (pintype "passive"))
      (node (ref "SW2") (pin "L2") (pinfunction "L2_L2") (pintype "passive"))
      (node (ref "SW2") (pin "P3") (pinfunction "A3_P3") (pintype "passive"))
      (node (ref "SW2") (pin "P6") (pinfunction "B3_P6") (pintype "passive"))
    )
    (net (code "33") (name "LED1") (class "Default")
      (node (ref "MCU1") (pin "EXT1-12") (pinfunction "PB5_EXT1-12") (pintype "bidirectional"))
      (node (ref "R2") (pin "1") (pinfunction "1_1") (pintype "passive"))
    )
    (net (code "34") (name "LED2") (class "Default")
      (node (ref "MCU1") (pin "EXT2-14") (pinfunction "PB10_EXT2-14") (pintype "bidirectional"))
      (node (ref "R1") (pin "2") (pinfunction "2_2") (pintype "passive"))
    )
    (net (code "35") (name "Net-(C19-Pad1)") (class "Default")
      (node (ref "C19") (pin "1") (pinfunction "1_1") (pintype "passive"))
      (node (ref "R36") (pin "1") (pinfunction "1_1") (pintype "passive"))
      (node (ref "R39") (pin "2") (pinfunction "2_2") (pintype "passive"))
    )
    (net (code "36") (name "Net-(C20-Pad-)") (class "Default")
      (node (ref "C20") (pin "-") (pinfunction "-_-") (pintype "passive"))
      (node (ref "R40") (pin "2") (pinfunction "2_2") (pintype "passive"))
    )
    (net (code "37") (name "Net-(D1-PadA)") (class "Default")
      (node (ref "D1") (pin "A") (pinfunction "A_A") (pintype "passive"))
      (node (ref "JP1") (pin "1") (pinfunction "1_1") (pintype "passive"))
      (node (ref "JP1") (pin "2") (pinfunction "2_2") (pintype "passive"))
    )
    (net (code "38") (name "Net-(D2-PadC)") (class "Default")
      (node (ref "D2") (pin "C") (pinfunction "C_C") (pintype "passive"))
      (node (ref "JP1") (pin "10") (pinfunction "10_10") (pintype "passive"))
      (node (ref "JP1") (pin "9") (pinfunction "9_9") (pintype "passive"))
    )
    (net (code "39") (name "Net-(DISP1-A)") (class "Default")
      (node (ref "DISP1") (pin "12") (pinfunction "A_12") (pintype "passive"))
      (node (ref "DISP2") (pin "12") (pinfunction "A_12") (pintype "passive"))
      (node (ref "R3") (pin "2") (pinfunction "2_2") (pintype "passive"))
    )
    (net (code "40") (name "Net-(DISP1-B)") (class "Default")
      (node (ref "DISP1") (pin "10") (pinfunction "B_10") (pintype "passive"))
      (node (ref "DISP2") (pin "10") (pinfunction "B_10") (pintype "passive"))
      (node (ref "R4") (pin "2") (pinfunction "2_2") (pintype "passive"))
    )
    (net (code "41") (name "Net-(DISP1-C)") (class "Default")
      (node (ref "DISP1") (pin "9") (pinfunction "C_9") (pintype "passive"))
      (node (ref "DISP2") (pin "9") (pinfunction "C_9") (pintype "passive"))
      (node (ref "R5") (pin "2") (pinfunction "2_2") (pintype "passive"))
    )
    (net (code "42") (name "Net-(DISP1-D)") (class "Default")
      (node (ref "DISP1") (pin "7") (pinfunction "D_7") (pintype "passive"))
      (node (ref "DISP2") (pin "7") (pinfunction "D_7") (pintype "passive"))
      (node (ref "R6") (pin "2") (pinfunction "2_2") (pintype "passive"))
    )
    (net (code "43") (name "Net-(DISP1-DP)") (class "Default")
      (node (ref "DISP1") (pin "8") (pinfunction "DP_8") (pintype "passive"))
      (node (ref "DISP2") (pin "8") (pinfunction "DP_8") (pintype "passive"))
      (node (ref "R17") (pin "2") (pinfunction "2_2") (pintype "passive"))
    )
    (net (code "44") (name "Net-(DISP1-E)") (class "Default")
      (node (ref "DISP1") (pin "1") (pinfunction "E_1") (pintype "passive"))
      (node (ref "DISP2") (pin "1") (pinfunction "E_1") (pintype "passive"))
      (node (ref "R7") (pin "2") (pinfunction "2_2") (pintype "passive"))
    )
    (net (code "45") (name "Net-(DISP1-F)") (class "Default")
      (node (ref "DISP1") (pin "18") (pinfunction "F_18") (pintype "passive"))
      (node (ref "DISP2") (pin "18") (pinfunction "F_18") (pintype "passive"))
      (node (ref "R8") (pin "2") (pinfunction "2_2") (pintype "passive"))
    )
    (net (code "46") (name "Net-(DISP1-G)") (class "Default")
      (node (ref "DISP1") (pin "17") (pinfunction "G_17") (pintype "passive"))
      (node (ref "DISP2") (pin "17") (pinfunction "G_17") (pintype "passive"))
      (node (ref "R9") (pin "2") (pinfunction "2_2") (pintype "passive"))
    )
    (net (code "47") (name "Net-(DISP1-H)") (class "Default")
      (node (ref "DISP1") (pin "15") (pinfunction "H_15") (pintype "passive"))
      (node (ref "DISP2") (pin "15") (pinfunction "H_15") (pintype "passive"))
      (node (ref "R10") (pin "2") (pinfunction "2_2") (pintype "passive"))
    )
    (net (code "48") (name "Net-(DISP1-J)") (class "Default")
      (node (ref "DISP1") (pin "14") (pinfunction "J_14") (pintype "passive"))
      (node (ref "DISP2") (pin "14") (pinfunction "J_14") (pintype "passive"))
      (node (ref "R11") (pin "2") (pinfunction "2_2") (pintype "passive"))
    )
    (net (code "49") (name "Net-(DISP1-K)") (class "Default")
      (node (ref "DISP1") (pin "6") (pinfunction "K_6") (pintype "passive"))
      (node (ref "DISP2") (pin "6") (pinfunction "K_6") (pintype "passive"))
      (node (ref "R12") (pin "2") (pinfunction "2_2") (pintype "passive"))
    )
    (net (code "50") (name "Net-(DISP1-K1)") (class "Default")
      (node (ref "DISP1") (pin "16") (pinfunction "K1_16") (pintype "passive"))
      (node (ref "Q1") (pin "C") (pinfunction "C_C") (pintype "passive"))
    )
    (net (code "51") (name "Net-(DISP1-K2)") (class "Default")
      (node (ref "DISP1") (pin "11") (pinfunction "K2_11") (pintype "passive"))
      (node (ref "Q2") (pin "C") (pinfunction "C_C") (pintype "passive"))
    )
    (net (code "52") (name "Net-(DISP1-L)") (class "Default")
      (node (ref "DISP1") (pin "5") (pinfunction "L_5") (pintype "passive"))
      (node (ref "DISP2") (pin "5") (pinfunction "L_5") (pintype "passive"))
      (node (ref "R13") (pin "2") (pinfunction "2_2") (pintype "passive"))
    )
    (net (code "53") (name "Net-(DISP1-M)") (class "Default")
      (node (ref "DISP1") (pin "4") (pinfunction "M_4") (pintype "passive"))
      (node (ref "DISP2") (pin "4") (pinfunction "M_4") (pintype "passive"))
      (node (ref "R14") (pin "2") (pinfunction "2_2") (pintype "passive"))
    )
    (net (code "54") (name "Net-(DISP1-N)") (class "Default")
      (node (ref "DISP1") (pin "2") (pinfunction "N_2") (pintype "passive"))
      (node (ref "DISP2") (pin "2") (pinfunction "N_2") (pintype "passive"))
      (node (ref "R15") (pin "2") (pinfunction "2_2") (pintype "passive"))
    )
    (net (code "55") (name "Net-(DISP1-P)") (class "Default")
      (node (ref "DISP1") (pin "13") (pinfunction "P_13") (pintype "passive"))
      (node (ref "DISP2") (pin "13") (pinfunction "P_13") (pintype "passive"))
      (node (ref "R16") (pin "2") (pinfunction "2_2") (pintype "passive"))
    )
    (net (code "56") (name "Net-(DISP2-K1)") (class "Default")
      (node (ref "DISP2") (pin "16") (pinfunction "K1_16") (pintype "passive"))
      (node (ref "Q3") (pin "C") (pinfunction "C_C") (pintype "passive"))
    )
    (net (code "57") (name "Net-(DISP2-K2)") (class "Default")
      (node (ref "DISP2") (pin "11") (pinfunction "K2_11") (pintype "passive"))
      (node (ref "Q4") (pin "C") (pinfunction "C_C") (pintype "passive"))
    )
    (net (code "58") (name "Net-(IC1A-QA)") (class "Default")
      (node (ref "IC1") (pin "15") (pinfunction "QA_15") (pintype "tri_state"))
      (node (ref "R3") (pin "1") (pinfunction "1_1") (pintype "passive"))
    )
    (net (code "59") (name "Net-(IC1A-QB)") (class "Default")
      (node (ref "IC1") (pin "1") (pinfunction "QB_1") (pintype "tri_state"))
      (node (ref "R4") (pin "1") (pinfunction "1_1") (pintype "passive"))
    )
    (net (code "60") (name "Net-(IC1A-QC)") (class "Default")
      (node (ref "IC1") (pin "2") (pinfunction "QC_2") (pintype "tri_state"))
      (node (ref "R5") (pin "1") (pinfunction "1_1") (pintype "passive"))
    )
    (net (code "61") (name "Net-(IC1A-QD)") (class "Default")
      (node (ref "IC1") (pin "3") (pinfunction "QD_3") (pintype "tri_state"))
      (node (ref "R6") (pin "1") (pinfunction "1_1") (pintype "passive"))
    )
    (net (code "62") (name "Net-(IC1A-QE)") (class "Default")
      (node (ref "IC1") (pin "4") (pinfunction "QE_4") (pintype "tri_state"))
      (node (ref "R7") (pin "1") (pinfunction "1_1") (pintype "passive"))
    )
    (net (code "63") (name "Net-(IC1A-QF)") (class "Default")
      (node (ref "IC1") (pin "5") (pinfunction "QF_5") (pintype "tri_state"))
      (node (ref "R8") (pin "1") (pinfunction "1_1") (pintype "passive"))
    )
    (net (code "64") (name "Net-(IC1A-QG)") (class "Default")
      (node (ref "IC1") (pin "6") (pinfunction "QG_6") (pintype "tri_state"))
      (node (ref "R9") (pin "1") (pinfunction "1_1") (pintype "passive"))
    )
    (net (code "65") (name "Net-(IC1A-QH)") (class "Default")
      (node (ref "IC1") (pin "7") (pinfunction "QH_7") (pintype "tri_state"))
      (node (ref "R10") (pin "1") (pinfunction "1_1") (pintype "passive"))
    )
    (net (code "66") (name "Net-(IC1A-QH*)") (class "Default")
      (node (ref "IC1") (pin "9") (pinfunction "QH*_9") (pintype "tri_state"))
      (node (ref "IC2") (pin "14") (pinfunction "SER_14") (pintype "input"))
    )
    (net (code "67") (name "Net-(IC2A-QA)") (class "Default")
      (node (ref "IC2") (pin "15") (pinfunction "QA_15") (pintype "tri_state"))
      (node (ref "R11") (pin "1") (pinfunction "1_1") (pintype "passive"))
    )
    (net (code "68") (name "Net-(IC2A-QB)") (class "Default")
      (node (ref "IC2") (pin "1") (pinfunction "QB_1") (pintype "tri_state"))
      (node (ref "R12") (pin "1") (pinfunction "1_1") (pintype "passive"))
    )
    (net (code "69") (name "Net-(IC2A-QC)") (class "Default")
      (node (ref "IC2") (pin "2") (pinfunction "QC_2") (pintype "tri_state"))
      (node (ref "R13") (pin "1") (pinfunction "1_1") (pintype "passive"))
    )
    (net (code "70") (name "Net-(IC2A-QD)") (class "Default")
      (node (ref "IC2") (pin "3") (pinfunction "QD_3") (pintype "tri_state"))
      (node (ref "R14") (pin "1") (pinfunction "1_1") (pintype "passive"))
    )
    (net (code "71") (name "Net-(IC2A-QE)") (class "Default")
      (node (ref "IC2") (pin "4") (pinfunction "QE_4") (pintype "tri_state"))
      (node (ref "R15") (pin "1") (pinfunction "1_1") (pintype "passive"))
    )
    (net (code "72") (name "Net-(IC2A-QF)") (class "Default")
      (node (ref "IC2") (pin "5") (pinfunction "QF_5") (pintype "tri_state"))
      (node (ref "R16") (pin "1") (pinfunction "1_1") (pintype "passive"))
    )
    (net (code "73") (name "Net-(IC2A-QG)") (class "Default")
      (node (ref "IC2") (pin "6") (pinfunction "QG_6") (pintype "tri_state"))
      (node (ref "R17") (pin "1") (pinfunction "1_1") (pintype "passive"))
    )
    (net (code "74") (name "Net-(IC4-VIN)") (class "Default")
      (node (ref "C6") (pin "+") (pinfunction "+_+") (pintype "passive"))
      (node (ref "IC4") (pin "2") (pinfunction "VIN_2") (pintype "input"))
      (node (ref "R49") (pin "1") (pinfunction "1_1") (pintype "passive"))
    )
    (net (code "75") (name "Net-(IC5A--IN)") (class "Default")
      (node (ref "C10") (pin "1") (pinfunction "1_1") (pintype "passive"))
      (node (ref "IC5") (pin "2") (pinfunction "-IN_2") (pintype "input"))
      (node (ref "R26") (pin "2") (pinfunction "2_2") (pintype "passive"))
      (node (ref "R27") (pin "2") (pinfunction "2_2") (pintype "passive"))
      (node (ref "R29") (pin "1") (pinfunction "1_1") (pintype "passive"))
    )
    (net (code "76") (name "Net-(IC5B--IN)") (class "Default")
      (node (ref "C9") (pin "1") (pinfunction "1_1") (pintype "passive"))
      (node (ref "IC5") (pin "6") (pinfunction "-IN_6") (pintype "input"))
      (node (ref "R24") (pin "2") (pinfunction "2_2") (pintype "passive"))
      (node (ref "R25") (pin "2") (pinfunction "2_2") (pintype "passive"))
      (node (ref "R28") (pin "1") (pinfunction "1_1") (pintype "passive"))
    )
    (net (code "77") (name "Net-(IC5C--IN)") (class "Default")
      (node (ref "C16") (pin "1") (pinfunction "1_1") (pintype "passive"))
      (node (ref "IC5") (pin "9") (pinfunction "-IN_9") (pintype "input"))
      (node (ref "R32") (pin "2") (pinfunction "2_2") (pintype "passive"))
      (node (ref "R33") (pin "2") (pinfunction "2_2") (pintype "passive"))
      (node (ref "R38") (pin "1") (pinfunction "1_1") (pintype "passive"))
    )
    (net (code "78") (name "Net-(IC5D--IN)") (class "Default")
      (node (ref "C15") (pin "1") (pinfunction "1_1") (pintype "passive"))
      (node (ref "IC5") (pin "13") (pinfunction "-IN_13") (pintype "input"))
      (node (ref "R34") (pin "2") (pinfunction "2_2") (pintype "passive"))
      (node (ref "R35") (pin "2") (pinfunction "2_2") (pintype "passive"))
      (node (ref "R37") (pin "1") (pinfunction "1_1") (pintype "passive"))
    )
    (net (code "79") (name "Net-(IC8A--IN)") (class "Default")
      (node (ref "C21") (pin "1") (pinfunction "1_1") (pintype "passive"))
      (node (ref "IC8") (pin "2") (pinfunction "-IN_2") (pintype "input"))
      (node (ref "R40") (pin "1") (pinfunction "1_1") (pintype "passive"))
      (node (ref "R43") (pin "2") (pinfunction "2_2") (pintype "passive"))
    )
    (net (code "80") (name "Net-(IC8A-OUT)") (class "Default")
      (node (ref "C21") (pin "2") (pinfunction "2_2") (pintype "passive"))
      (node (ref "IC8") (pin "1") (pinfunction "OUT_1") (pintype "output"))
      (node (ref "R44") (pin "2") (pinfunction "2_2") (pintype "passive"))
    )
    (net (code "81") (name "Net-(IC8B-+IN)") (class "Default")
      (node (ref "C17") (pin "1") (pinfunction "1_1") (pintype "passive"))
      (node (ref "IC8") (pin "5") (pinfunction "+IN_5") (pintype "input"))
      (node (ref "R39") (pin "1") (pinfunction "1_1") (pintype "passive"))
    )
    (net (code "82") (name "Net-(IC8B--IN)") (class "Default")
      (node (ref "C19") (pin "2") (pinfunction "2_2") (pintype "passive"))
      (node (ref "C20") (pin "+") (pinfunction "+_+") (pintype "passive"))
      (node (ref "IC8") (pin "6") (pinfunction "-IN_6") (pintype "input"))
      (node (ref "IC8") (pin "7") (pinfunction "OUT_7") (pintype "output"))
    )
    (net (code "83") (name "Net-(J1-3)") (class "Default")
      (node (ref "J1") (pin "P3") (pinfunction "3_P3") (pintype "passive"))
      (node (ref "R22") (pin "1") (pinfunction "1_1") (pintype "passive"))
    )
    (net (code "84") (name "Net-(J6-3)") (class "Default")
      (node (ref "J6") (pin "P3") (pinfunction "3_P3") (pintype "passive"))
      (node (ref "R43") (pin "1") (pinfunction "1_1") (pintype "passive"))
      (node (ref "R44") (pin "1") (pinfunction "1_1") (pintype "passive"))
    )
    (net (code "85") (name "Net-(LED1-PadA)") (class "Default")
      (node (ref "LED1") (pin "A") (pinfunction "A_A") (pintype "passive"))
      (node (ref "R2") (pin "2") (pinfunction "2_2") (pintype "passive"))
    )
    (net (code "86") (name "Net-(Q1-PadB)") (class "Default")
      (node (ref "Q1") (pin "B") (pinfunction "B_B") (pintype "passive"))
      (node (ref "R18") (pin "2") (pinfunction "2_2") (pintype "passive"))
    )
    (net (code "87") (name "Net-(Q2-PadB)") (class "Default")
      (node (ref "Q2") (pin "B") (pinfunction "B_B") (pintype "passive"))
      (node (ref "R19") (pin "2") (pinfunction "2_2") (pintype "passive"))
    )
    (net (code "88") (name "Net-(Q3-PadB)") (class "Default")
      (node (ref "Q3") (pin "B") (pinfunction "B_B") (pintype "passive"))
      (node (ref "R20") (pin "2") (pinfunction "2_2") (pintype "passive"))
    )
    (net (code "89") (name "Net-(Q4-PadB)") (class "Default")
      (node (ref "Q4") (pin "B") (pinfunction "B_B") (pintype "passive"))
      (node (ref "R21") (pin "2") (pinfunction "2_2") (pintype "passive"))
    )
    (net (code "90") (name "Net-(Q5-PadB)") (class "Default")
      (node (ref "Q5") (pin "B") (pinfunction "B_B") (pintype "passive"))
      (node (ref "R22") (pin "2") (pinfunction "2_2") (pintype "passive"))
    )
    (net (code "91") (name "Net-(R1-Pad1)") (class "Default")
      (node (ref "R1") (pin "1") (pinfunction "1_1") (pintype "passive"))
      (node (ref "SW2") (pin "L1") (pinfunction "L1_L1") (pintype "passive"))
    )
    (net (code "92") (name "PARAM1_CV") (class "Default")
      (node (ref "C10") (pin "2") (pinfunction "2_2") (pintype "passive"))
      (node (ref "IC5") (pin "1") (pinfunction "OUT_1") (pintype "output"))
      (node (ref "MCU1") (pin "EXT2-7") (pinfunction "PA2_EXT2-7") (pintype "bidirectional"))
      (node (ref "R29") (pin "2") (pinfunction "2_2") (pintype "passive"))
    )
    (net (code "93") (name "PARAM2_CV") (class "Default")
      (node (ref "C9") (pin "2") (pinfunction "2_2") (pintype "passive"))
      (node (ref "IC5") (pin "7") (pinfunction "OUT_7") (pintype "output"))
      (node (ref "MCU1") (pin "EXT1-26") (pinfunction "PB1_EXT1-26") (pintype "bidirectional"))
      (node (ref "R28") (pin "2") (pinfunction "2_2") (pintype "passive"))
    )
    (net (code "94") (name "PITCH_CV") (class "Default")
      (node (ref "C16") (pin "2") (pinfunction "2_2") (pintype "passive"))
      (node (ref "IC5") (pin "8") (pinfunction "OUT_8") (pintype "output"))
      (node (ref "MCU1") (pin "EXT2-10") (pinfunction "PA3_EXT2-10") (pintype "bidirectional"))
      (node (ref "R38") (pin "2") (pinfunction "2_2") (pintype "passive"))
    )
    (net (code "95") (name "SWITCH1") (class "Default")
      (node (ref "MCU1") (pin "EXT2-15") (pinfunction "PB11_EXT2-15") (pintype "bidirectional"))
      (node (ref "S1") (pin "3") (pinfunction "3_3") (pintype "passive"))
      (node (ref "S1") (pin "4") (pinfunction "4_4") (pintype "passive"))
    )
    (net (code "96") (name "SWITCH2") (class "Default")
      (node (ref "MCU1") (pin "EXT2-13") (pinfunction "PC5_EXT2-13") (pintype "bidirectional"))
      (node (ref "SW2") (pin "P2") (pinfunction "A2_P2") (pintype "passive"))
      (node (ref "SW2") (pin "P5") (pinfunction "B2_P5") (pintype "passive"))
    )
    (net (code "97") (name "TIMBRE") (class "Default")
      (node (ref "J4") (pin "P3") (pinfunction "3_P3") (pintype "passive"))
      (node (ref "R27") (pin "1") (pinfunction "1_1") (pintype "passive"))
    )
    (net (code "98") (name "UART_LOGGER") (class "Default")
      (node (ref "MCU1") (pin "EXT1-13") (pinfunction "PB6_EXT1-13") (pintype "bidirectional"))
      (node (ref "TP1") (pin "P$1") (pinfunction "1_P$1") (pintype "bidirectional"))
    )
    (net (code "99") (name "VCC") (class "Default")
      (node (ref "C13") (pin "1") (pinfunction "1_1") (pintype "passive"))
      (node (ref "C4") (pin "+") (pinfunction "+_+") (pintype "passive"))
      (node (ref "D1") (pin "C") (pinfunction "C_C") (pintype "passive"))
      (node (ref "IC8") (pin "8") (pinfunction "V+_8") (pintype "power_in"))
      (node (ref "R49") (pin "2") (pinfunction "2_2") (pintype "passive"))
    )
    (net (code "100") (name "VEE") (class "Default")
      (node (ref "C14") (pin "2") (pinfunction "2_2") (pintype "passive"))
      (node (ref "C5") (pin "-") (pinfunction "-_-") (pintype "passive"))
      (node (ref "D2") (pin "A") (pinfunction "A_A") (pintype "passive"))
      (node (ref "IC8") (pin "4") (pinfunction "V-_4") (pintype "power_in"))
      (node (ref "R31") (pin "1") (pinfunction "1_1") (pintype "passive"))
    )
    (net (code "101") (name "VOCT") (class "Default")
      (node (ref "J2") (pin "P3") (pinfunction "3_P3") (pintype "passive"))
      (node (ref "R33") (pin "1") (pinfunction "1_1") (pintype "passive"))
    )
    (net (code "102") (name "unconnected-(IC2A-QH*-Pad9)") (class "Default")
      (node (ref "IC2") (pin "9") (pinfunction "QH*_9") (pintype "tri_state"))
    )
    (net (code "103") (name "unconnected-(IC2A-QH-Pad7)") (class "Default")
      (node (ref "IC2") (pin "7") (pinfunction "QH_7") (pintype "tri_state"))
    )
    (net (code "104") (name "unconnected-(J2-2-PadP2)") (class "Default")
      (node (ref "J2") (pin "P2") (pinfunction "2_P2") (pintype "passive"))
    )
    (net (code "105") (name "unconnected-(J3-2-PadP2)") (class "Default")
      (node (ref "J3") (pin "P2") (pinfunction "2_P2") (pintype "passive"))
    )
    (net (code "106") (name "unconnected-(J4-2-PadP2)") (class "Default")
      (node (ref "J4") (pin "P2") (pinfunction "2_P2") (pintype "passive"))
    )
    (net (code "107") (name "unconnected-(J5-2-PadP2)") (class "Default")
      (node (ref "J5") (pin "P2") (pinfunction "2_P2") (pintype "passive"))
    )
    (net (code "108") (name "unconnected-(J6-2-PadP2)") (class "Default")
      (node (ref "J6") (pin "P2") (pinfunction "2_P2") (pintype "passive"))
    )
    (net (code "109") (name "unconnected-(MCU1-NRST-PadEXT1-25)") (class "Default")
      (node (ref "MCU1") (pin "EXT1-25") (pinfunction "NRST_EXT1-25") (pintype "bidirectional"))
    )
    (net (code "110") (name "unconnected-(MCU1-PA0-PadEXT2-4)") (class "Default")
      (node (ref "MCU1") (pin "EXT2-4") (pinfunction "PA0_EXT2-4") (pintype "bidirectional"))
    )
    (net (code "111") (name "unconnected-(MCU1-PA11-PadEXT1-1)") (class "Default")
      (node (ref "MCU1") (pin "EXT1-1") (pinfunction "PA11_EXT1-1") (pintype "bidirectional"))
    )
    (net (code "112") (name "unconnected-(MCU1-PA12-PadEXT1-3)") (class "Default")
      (node (ref "MCU1") (pin "EXT1-3") (pinfunction "PA12_EXT1-3") (pintype "bidirectional"))
    )
    (net (code "113") (name "unconnected-(MCU1-PB0-PadEXT1-21)") (class "Default")
      (node (ref "MCU1") (pin "EXT1-21") (pinfunction "PB0_EXT1-21") (pintype "bidirectional"))
    )
    (net (code "114") (name "unconnected-(MCU1-PB7-PadEXT1-15)") (class "Default")
      (node (ref "MCU1") (pin "EXT1-15") (pinfunction "PB7_EXT1-15") (pintype "bidirectional"))
    )
    (net (code "115") (name "unconnected-(MCU1-PB8-PadEXT1-16)") (class "Default")
      (node (ref "MCU1") (pin "EXT1-16") (pinfunction "PB8_EXT1-16") (pintype "bidirectional"))
    )
    (net (code "116") (name "unconnected-(MCU1-PB9-PadEXT1-17)") (class "Default")
      (node (ref "MCU1") (pin "EXT1-17") (pinfunction "PB9_EXT1-17") (pintype "bidirectional"))
    )
    (net (code "117") (name "unconnected-(MCU1-PC4-PadEXT2-12)") (class "Default")
      (node (ref "MCU1") (pin "EXT2-12") (pinfunction "PC4_EXT2-12") (pintype "bidirectional"))
    )
    (net (code "118") (name "unconnected-(MCU1-PC6-PadEXT2-20)") (class "Default")
      (node (ref "MCU1") (pin "EXT2-20") (pinfunction "PC6_EXT2-20") (pintype "bidirectional"))
    )
    (net (code "119") (name "unconnected-(MCU1-PC11-PadEXT1-9)") (class "Default")
      (node (ref "MCU1") (pin "EXT1-9") (pinfunction "PC11_EXT1-9") (pintype "bidirectional"))
    )
    (net (code "120") (name "unconnected-(MCU1-PC13-PadEXT1-24)") (class "Default")
      (node (ref "MCU1") (pin "EXT1-24") (pinfunction "PC13_EXT1-24") (pintype "bidirectional"))
    )
    (net (code "121") (name "unconnected-(MCU1-VBAT-PadEXT1-23)") (class "Default")
      (node (ref "MCU1") (pin "EXT1-23") (pinfunction "VBAT_EXT1-23") (pintype "bidirectional"))
    )
    (net (code "122") (name "unconnected-(MCU1-VUSB-PadEXT2-23)") (class "Default")
      (node (ref "MCU1") (pin "EXT2-23") (pinfunction "VUSB_EXT2-23") (pintype "bidirectional"))
    )
    (net (code "123") (name "unconnected-(SW2A-A1-PadP1)") (class "Default")
      (node (ref "SW2") (pin "P1") (pinfunction "A1_P1") (pintype "passive"))
    )
    (net (code "124") (name "unconnected-(SW2A-B1-PadP4)") (class "Default")
      (node (ref "SW2") (pin "P4") (pinfunction "B1_P4") (pintype "passive"))
    )
  )
)
